# dsky_md_2_4v.net
KiCad netlist of a schematic drawn in EAGLE
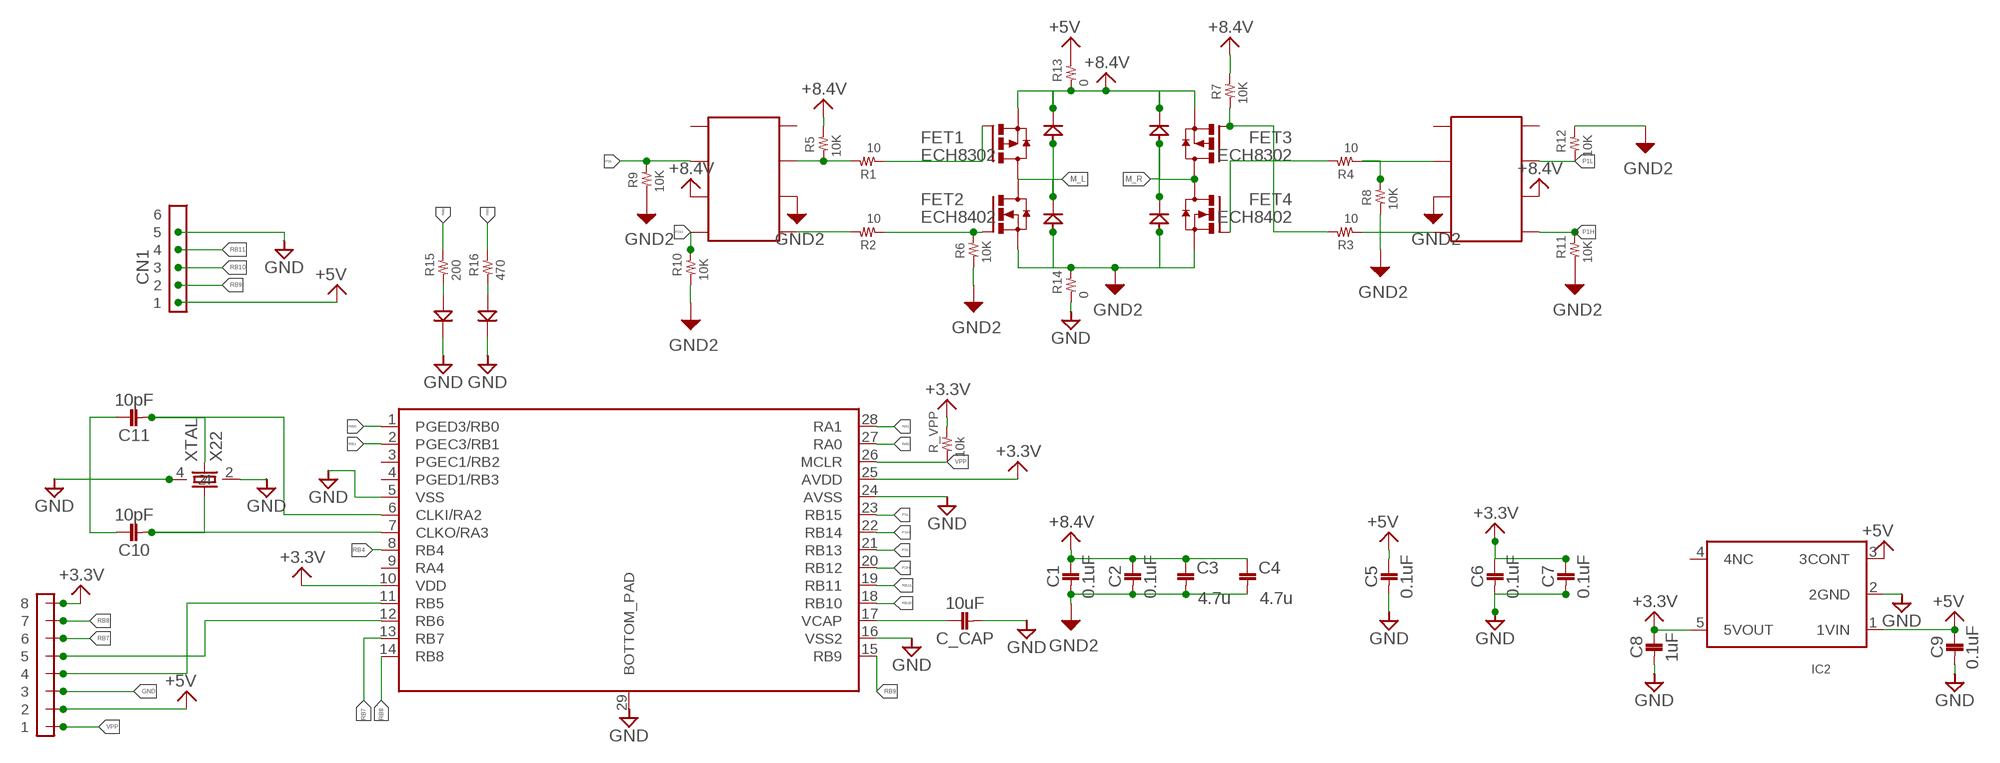
[diagram p0: schematic, sheet 1]

(export (version "E")
  (design (tool "Eeschema 10.0.6"))
  (components
    (comp (ref "C1")
      (value "0.1uF")
      (footprint "eagle-import:1608")
      (libsource (lib "eagle-import") (part "1608"))
    )
    (comp (ref "C2")
      (value "0.1uF")
      (footprint "eagle-import:1608")
      (libsource (lib "eagle-import") (part "1608"))
    )
    (comp (ref "C3")
      (value "4.7u")
      (footprint "eagle-import:2012")
      (libsource (lib "eagle-import") (part "2012"))
    )
    (comp (ref "C4")
      (value "4.7u")
      (footprint "eagle-import:2012")
      (libsource (lib "eagle-import") (part "2012"))
    )
    (comp (ref "C5")
      (value "0.1uF")
      (footprint "eagle-import:1608")
      (libsource (lib "eagle-import") (part "1608"))
    )
    (comp (ref "C6")
      (value "0.1uF")
      (footprint "eagle-import:1608")
      (libsource (lib "eagle-import") (part "1608"))
    )
    (comp (ref "C7")
      (value "0.1uF")
      (footprint "eagle-import:1608")
      (libsource (lib "eagle-import") (part "1608"))
    )
    (comp (ref "C8")
      (value "1uF")
      (footprint "eagle-import:1608")
      (libsource (lib "eagle-import") (part "1608"))
    )
    (comp (ref "C9")
      (value "0.1uF")
      (footprint "eagle-import:1608")
      (libsource (lib "eagle-import") (part "1608"))
    )
    (comp (ref "C10")
      (value "10pF")
      (footprint "eagle-import:1608")
      (libsource (lib "eagle-import") (part "1608"))
    )
    (comp (ref "C11")
      (value "10pF")
      (footprint "eagle-import:1608")
      (libsource (lib "eagle-import") (part "1608"))
    )
    (comp (ref "CN1")
      (value "FH12-6S-0.5")
      (footprint "eagle-import:FPC6")
      (libsource (lib "eagle-import") (part "FH12-6S-0.5"))
    )
    (comp (ref "C_CAP")
      (value "10uF")
      (footprint "eagle-import:1608")
      (libsource (lib "eagle-import") (part "1608"))
    )
    (comp (ref "D1")
      (value "SS2040")
      (footprint "eagle-import:SOD-123FL")
      (libsource (lib "eagle-import") (part "SS2040"))
    )
    (comp (ref "D2")
      (value "SS2040")
      (footprint "eagle-import:SOD-123FL")
      (libsource (lib "eagle-import") (part "SS2040"))
    )
    (comp (ref "D3")
      (value "SS2040")
      (footprint "eagle-import:SOD-123FL")
      (libsource (lib "eagle-import") (part "SS2040"))
    )
    (comp (ref "D4")
      (value "SS2040")
      (footprint "eagle-import:SOD-123FL")
      (libsource (lib "eagle-import") (part "SS2040"))
    )
    (comp (ref "FET1")
      (value "ECH8302")
      (footprint "eagle-import:ECH8")
      (libsource (lib "eagle-import") (part "ECH83"))
    )
    (comp (ref "FET2")
      (value "ECH8402")
      (footprint "eagle-import:ECH8")
      (libsource (lib "eagle-import") (part "ECH84"))
    )
    (comp (ref "FET3")
      (value "ECH8302")
      (footprint "eagle-import:ECH8")
      (libsource (lib "eagle-import") (part "ECH83"))
    )
    (comp (ref "FET4")
      (value "ECH8402")
      (footprint "eagle-import:ECH8")
      (libsource (lib "eagle-import") (part "ECH84"))
    )
    (comp (ref "IC1")
      (value "DSPIC33EP32MC202")
      (footprint "eagle-import:QFN-S28_6X6MC")
      (libsource (lib "eagle-import") (part "DSPIC33EP32MC202"))
    )
    (comp (ref "IC2")
      (value "NJM2866F33")
      (footprint "eagle-import:SSOP5-P-0.95")
      (libsource (lib "eagle-import") (part "TAR5SB"))
    )
    (comp (ref "IC3")
      (value "TC1427COA")
      (footprint "eagle-import:SOIC8")
      (libsource (lib "eagle-import") (part "TC1427COA"))
    )
    (comp (ref "IC4")
      (value "TC1427COA")
      (footprint "eagle-import:SOIC8")
      (libsource (lib "eagle-import") (part "TC1427COA"))
    )
    (comp (ref "LED1")
      (value "1608")
      (footprint "eagle-import:1608")
      (libsource (lib "eagle-import") (part "LED_1608"))
    )
    (comp (ref "LED2")
      (value "1608")
      (footprint "eagle-import:1608")
      (libsource (lib "eagle-import") (part "LED_1608"))
    )
    (comp (ref "PIN_HEADER")
      (value "PIN_HEADER_8")
      (footprint "eagle-import:PIN_HEADER_8")
      (libsource (lib "eagle-import") (part "PIN_HEADER_8"))
    )
    (comp (ref "R1")
      (value "10")
      (footprint "eagle-import:1608")
      (libsource (lib "eagle-import") (part "RESISTOR__SMD"))
    )
    (comp (ref "R2")
      (value "10")
      (footprint "eagle-import:1608")
      (libsource (lib "eagle-import") (part "RESISTOR__SMD"))
    )
    (comp (ref "R3")
      (value "10")
      (footprint "eagle-import:1608")
      (libsource (lib "eagle-import") (part "RESISTOR__SMD"))
    )
    (comp (ref "R4")
      (value "10")
      (footprint "eagle-import:1608")
      (libsource (lib "eagle-import") (part "RESISTOR__SMD"))
    )
    (comp (ref "R5")
      (value "10K")
      (footprint "eagle-import:1608")
      (libsource (lib "eagle-import") (part "RESISTOR__SMD"))
    )
    (comp (ref "R6")
      (value "10K")
      (footprint "eagle-import:1608")
      (libsource (lib "eagle-import") (part "RESISTOR__SMD"))
    )
    (comp (ref "R7")
      (value "10K")
      (footprint "eagle-import:1608")
      (libsource (lib "eagle-import") (part "RESISTOR__SMD"))
    )
    (comp (ref "R8")
      (value "10K")
      (footprint "eagle-import:1608")
      (libsource (lib "eagle-import") (part "RESISTOR__SMD"))
    )
    (comp (ref "R9")
      (value "10K")
      (footprint "eagle-import:1608")
      (libsource (lib "eagle-import") (part "RESISTOR__SMD"))
    )
    (comp (ref "R10")
      (value "10K")
      (footprint "eagle-import:1608")
      (libsource (lib "eagle-import") (part "RESISTOR__SMD"))
    )
    (comp (ref "R11")
      (value "10K")
      (footprint "eagle-import:1608")
      (libsource (lib "eagle-import") (part "RESISTOR__SMD"))
    )
    (comp (ref "R12")
      (value "10K")
      (footprint "eagle-import:1608")
      (libsource (lib "eagle-import") (part "RESISTOR__SMD"))
    )
    (comp (ref "R13")
      (value "0")
      (footprint "eagle-import:1608")
      (libsource (lib "eagle-import") (part "RESISTOR__SMD"))
    )
    (comp (ref "R14")
      (value "0")
      (footprint "eagle-import:1608")
      (libsource (lib "eagle-import") (part "RESISTOR__SMD"))
    )
    (comp (ref "R15")
      (value "200")
      (footprint "eagle-import:1608")
      (libsource (lib "eagle-import") (part "RESISTOR__SMD"))
    )
    (comp (ref "R16")
      (value "470")
      (footprint "eagle-import:1608")
      (libsource (lib "eagle-import") (part "RESISTOR__SMD"))
    )
    (comp (ref "R_VPP")
      (value "10k")
      (footprint "eagle-import:1608")
      (libsource (lib "eagle-import") (part "RESISTOR__SMD"))
    )
    (comp (ref "XTAL")
      (value "X22")
      (footprint "eagle-import:SMD_X22")
      (libsource (lib "eagle-import") (part "X22"))
    )
  )
  (nets
    (net (code "1") (name "+3.3V") (class "Default")
      (node (ref "C6") (pin "P$1") (pinfunction "1_P$1") (pintype "passive"))
      (node (ref "C7") (pin "P$1") (pinfunction "1_P$1") (pintype "passive"))
      (node (ref "C8") (pin "P$1") (pinfunction "1_P$1") (pintype "passive"))
      (node (ref "IC1") (pin "10") (pinfunction "VDD_10") (pintype "bidirectional"))
      (node (ref "IC1") (pin "25") (pinfunction "AVDD_25") (pintype "bidirectional"))
      (node (ref "IC2") (pin "5") (pinfunction "5VOUT_5") (pintype "bidirectional"))
      (node (ref "PIN_HEADER") (pin "8") (pinfunction "8_8") (pintype "bidirectional"))
      (node (ref "R_VPP") (pin "2") (pinfunction "P$2_2") (pintype "passive"))
    )
    (net (code "2") (name "+5V") (class "Default")
      (node (ref "C5") (pin "P$1") (pinfunction "1_P$1") (pintype "passive"))
      (node (ref "C9") (pin "P$1") (pinfunction "1_P$1") (pintype "passive"))
      (node (ref "CN1") (pin "P1") (pinfunction "1_P1") (pintype "bidirectional"))
      (node (ref "IC2") (pin "1") (pinfunction "1VIN_1") (pintype "bidirectional"))
      (node (ref "IC2") (pin "3") (pinfunction "3CONT_3") (pintype "bidirectional"))
      (node (ref "PIN_HEADER") (pin "2") (pinfunction "2_2") (pintype "bidirectional"))
      (node (ref "R13") (pin "2") (pinfunction "P$2_2") (pintype "passive"))
    )
    (net (code "3") (name "+8.4V") (class "Default")
      (node (ref "C1") (pin "P$1") (pinfunction "1_P$1") (pintype "passive"))
      (node (ref "C2") (pin "P$1") (pinfunction "1_P$1") (pintype "passive"))
      (node (ref "C3") (pin "1") (pinfunction "1_1") (pintype "passive"))
      (node (ref "C4") (pin "1") (pinfunction "1_1") (pintype "passive"))
      (node (ref "D1") (pin "2") (pinfunction "PK_2") (pintype "bidirectional"))
      (node (ref "D3") (pin "2") (pinfunction "PK_2") (pintype "bidirectional"))
      (node (ref "FET1") (pin "1") (pinfunction "S_1") (pintype "passive"))
      (node (ref "FET1") (pin "2") (pinfunction "S_2") (pintype "passive"))
      (node (ref "FET1") (pin "3") (pinfunction "S_3") (pintype "passive"))
      (node (ref "FET3") (pin "1") (pinfunction "S_1") (pintype "passive"))
      (node (ref "FET3") (pin "2") (pinfunction "S_2") (pintype "passive"))
      (node (ref "FET3") (pin "3") (pinfunction "S_3") (pintype "passive"))
      (node (ref "IC3") (pin "3") (pinfunction "3_GND_3") (pintype "bidirectional"))
      (node (ref "IC4") (pin "3") (pinfunction "3_GND_3") (pintype "bidirectional"))
      (node (ref "R13") (pin "1") (pinfunction "P$1_1") (pintype "passive"))
      (node (ref "R5") (pin "2") (pinfunction "P$2_2") (pintype "passive"))
      (node (ref "R7") (pin "2") (pinfunction "P$2_2") (pintype "passive"))
    )
    (net (code "4") (name "GND") (class "Default")
      (node (ref "C10") (pin "P$1") (pinfunction "1_P$1") (pintype "passive"))
      (node (ref "C11") (pin "P$1") (pinfunction "1_P$1") (pintype "passive"))
      (node (ref "C5") (pin "P$2") (pinfunction "2_P$2") (pintype "passive"))
      (node (ref "C6") (pin "P$2") (pinfunction "2_P$2") (pintype "passive"))
      (node (ref "C7") (pin "P$2") (pinfunction "2_P$2") (pintype "passive"))
      (node (ref "C8") (pin "P$2") (pinfunction "2_P$2") (pintype "passive"))
      (node (ref "C9") (pin "P$2") (pinfunction "2_P$2") (pintype "passive"))
      (node (ref "CN1") (pin "P5") (pinfunction "5_P5") (pintype "bidirectional"))
      (node (ref "CN1") (pin "P_NC1") (pinfunction "5_P_NC1") (pintype "bidirectional"))
      (node (ref "CN1") (pin "P_NC2") (pinfunction "5_P_NC2") (pintype "bidirectional"))
      (node (ref "C_CAP") (pin "P$2") (pinfunction "2_P$2") (pintype "passive"))
      (node (ref "IC1") (pin "16") (pinfunction "VSS2_16") (pintype "power_in"))
      (node (ref "IC1") (pin "24") (pinfunction "AVSS_24") (pintype "bidirectional"))
      (node (ref "IC1") (pin "29") (pinfunction "BOTTOM_PAD_29") (pintype "bidirectional"))
      (node (ref "IC1") (pin "5") (pinfunction "VSS_5") (pintype "power_in"))
      (node (ref "IC2") (pin "2") (pinfunction "2GND_2") (pintype "bidirectional"))
      (node (ref "LED1") (pin "2") (pinfunction "K_2") (pintype "bidirectional"))
      (node (ref "LED2") (pin "2") (pinfunction "K_2") (pintype "bidirectional"))
      (node (ref "PIN_HEADER") (pin "3") (pinfunction "3_3") (pintype "bidirectional"))
      (node (ref "R14") (pin "1") (pinfunction "P$1_1") (pintype "passive"))
      (node (ref "XTAL") (pin "2") (pinfunction "2_2") (pintype "bidirectional"))
      (node (ref "XTAL") (pin "4") (pinfunction "4_4") (pintype "bidirectional"))
    )
    (net (code "5") (name "GND2") (class "Default")
      (node (ref "C1") (pin "P$2") (pinfunction "2_P$2") (pintype "passive"))
      (node (ref "C2") (pin "P$2") (pinfunction "2_P$2") (pintype "passive"))
      (node (ref "C3") (pin "2") (pinfunction "2_2") (pintype "passive"))
      (node (ref "C4") (pin "2") (pinfunction "2_2") (pintype "passive"))
      (node (ref "D2") (pin "1") (pinfunction "PA_1") (pintype "bidirectional"))
      (node (ref "D4") (pin "1") (pinfunction "PA_1") (pintype "bidirectional"))
      (node (ref "FET2") (pin "1") (pinfunction "S_1") (pintype "passive"))
      (node (ref "FET2") (pin "2") (pinfunction "S_2") (pintype "passive"))
      (node (ref "FET2") (pin "3") (pinfunction "S_3") (pintype "passive"))
      (node (ref "FET4") (pin "1") (pinfunction "S_1") (pintype "passive"))
      (node (ref "FET4") (pin "2") (pinfunction "S_2") (pintype "passive"))
      (node (ref "FET4") (pin "3") (pinfunction "S_3") (pintype "passive"))
      (node (ref "IC3") (pin "6") (pinfunction "6_VDD_6") (pintype "bidirectional"))
      (node (ref "IC4") (pin "6") (pinfunction "6_VDD_6") (pintype "bidirectional"))
      (node (ref "R10") (pin "1") (pinfunction "P$1_1") (pintype "passive"))
      (node (ref "R11") (pin "1") (pinfunction "P$1_1") (pintype "passive"))
      (node (ref "R12") (pin "2") (pinfunction "P$2_2") (pintype "passive"))
      (node (ref "R14") (pin "2") (pinfunction "P$2_2") (pintype "passive"))
      (node (ref "R6") (pin "1") (pinfunction "P$1_1") (pintype "passive"))
      (node (ref "R8") (pin "1") (pinfunction "P$1_1") (pintype "passive"))
      (node (ref "R9") (pin "1") (pinfunction "P$1_1") (pintype "passive"))
    )
    (net (code "6") (name "M_L") (class "Default")
      (node (ref "D1") (pin "1") (pinfunction "PA_1") (pintype "bidirectional"))
      (node (ref "D2") (pin "2") (pinfunction "PK_2") (pintype "bidirectional"))
      (node (ref "FET1") (pin "5") (pinfunction "D_5") (pintype "passive"))
      (node (ref "FET1") (pin "6") (pinfunction "D_6") (pintype "passive"))
      (node (ref "FET1") (pin "7") (pinfunction "D_7") (pintype "passive"))
      (node (ref "FET1") (pin "8") (pinfunction "D_8") (pintype "passive"))
      (node (ref "FET2") (pin "5") (pinfunction "D_5") (pintype "passive"))
      (node (ref "FET2") (pin "6") (pinfunction "D_6") (pintype "passive"))
      (node (ref "FET2") (pin "7") (pinfunction "D_7") (pintype "passive"))
      (node (ref "FET2") (pin "8") (pinfunction "D_8") (pintype "passive"))
    )
    (net (code "7") (name "M_R") (class "Default")
      (node (ref "D3") (pin "1") (pinfunction "PA_1") (pintype "bidirectional"))
      (node (ref "D4") (pin "2") (pinfunction "PK_2") (pintype "bidirectional"))
      (node (ref "FET3") (pin "5") (pinfunction "D_5") (pintype "passive"))
      (node (ref "FET3") (pin "6") (pinfunction "D_6") (pintype "passive"))
      (node (ref "FET3") (pin "7") (pinfunction "D_7") (pintype "passive"))
      (node (ref "FET3") (pin "8") (pinfunction "D_8") (pintype "passive"))
      (node (ref "FET4") (pin "5") (pinfunction "D_5") (pintype "passive"))
      (node (ref "FET4") (pin "6") (pinfunction "D_6") (pintype "passive"))
      (node (ref "FET4") (pin "7") (pinfunction "D_7") (pintype "passive"))
      (node (ref "FET4") (pin "8") (pinfunction "D_8") (pintype "passive"))
    )
    (net (code "8") (name "Net-(C10-2)") (class "Default")
      (node (ref "C10") (pin "P$2") (pinfunction "2_P$2") (pintype "passive"))
      (node (ref "IC1") (pin "7") (pinfunction "CLKO/RA3_7") (pintype "bidirectional"))
      (node (ref "XTAL") (pin "1") (pinfunction "1_1") (pintype "passive"))
    )
    (net (code "9") (name "Net-(C11-2)") (class "Default")
      (node (ref "C11") (pin "P$2") (pinfunction "2_P$2") (pintype "passive"))
      (node (ref "IC1") (pin "6") (pinfunction "CLKI/RA2_6") (pintype "bidirectional"))
      (node (ref "XTAL") (pin "3") (pinfunction "3_3") (pintype "passive"))
    )
    (net (code "10") (name "Net-(C_CAP-1)") (class "Default")
      (node (ref "C_CAP") (pin "P$1") (pinfunction "1_P$1") (pintype "passive"))
      (node (ref "IC1") (pin "17") (pinfunction "VCAP_17") (pintype "bidirectional"))
    )
    (net (code "11") (name "Net-(FET1-G)") (class "Default")
      (node (ref "FET1") (pin "4") (pinfunction "G_4") (pintype "passive"))
      (node (ref "R1") (pin "1") (pinfunction "P$1_1") (pintype "passive"))
    )
    (net (code "12") (name "Net-(FET2-G)") (class "Default")
      (node (ref "FET2") (pin "4") (pinfunction "G_4") (pintype "passive"))
      (node (ref "R2") (pin "1") (pinfunction "P$1_1") (pintype "passive"))
      (node (ref "R6") (pin "2") (pinfunction "P$2_2") (pintype "passive"))
    )
    (net (code "13") (name "Net-(FET3-G)") (class "Default")
      (node (ref "FET3") (pin "4") (pinfunction "G_4") (pintype "passive"))
      (node (ref "R3") (pin "2") (pinfunction "P$2_2") (pintype "passive"))
      (node (ref "R7") (pin "1") (pinfunction "P$1_1") (pintype "passive"))
    )
    (net (code "14") (name "Net-(FET4-G)") (class "Default")
      (node (ref "FET4") (pin "4") (pinfunction "G_4") (pintype "passive"))
      (node (ref "R4") (pin "2") (pinfunction "P$2_2") (pintype "passive"))
    )
    (net (code "15") (name "Net-(IC1-RB5)") (class "Default")
      (node (ref "IC1") (pin "11") (pinfunction "RB5_11") (pintype "bidirectional"))
      (node (ref "PIN_HEADER") (pin "4") (pinfunction "4_4") (pintype "bidirectional"))
    )
    (net (code "16") (name "Net-(IC1-RB6)") (class "Default")
      (node (ref "IC1") (pin "12") (pinfunction "RB6_12") (pintype "bidirectional"))
      (node (ref "PIN_HEADER") (pin "5") (pinfunction "5_5") (pintype "bidirectional"))
    )
    (net (code "17") (name "Net-(IC3-5_OUT_B)") (class "Default")
      (node (ref "IC3") (pin "5") (pinfunction "5_OUT_B_5") (pintype "bidirectional"))
      (node (ref "R2") (pin "2") (pinfunction "P$2_2") (pintype "passive"))
    )
    (net (code "18") (name "Net-(IC3-7_OUT_A)") (class "Default")
      (node (ref "IC3") (pin "7") (pinfunction "7_OUT_A_7") (pintype "bidirectional"))
      (node (ref "R1") (pin "2") (pinfunction "P$2_2") (pintype "passive"))
      (node (ref "R5") (pin "1") (pinfunction "P$1_1") (pintype "passive"))
    )
    (net (code "19") (name "Net-(IC4-5_OUT_B)") (class "Default")
      (node (ref "IC4") (pin "5") (pinfunction "5_OUT_B_5") (pintype "bidirectional"))
      (node (ref "R3") (pin "1") (pinfunction "P$1_1") (pintype "passive"))
    )
    (net (code "20") (name "Net-(IC4-7_OUT_A)") (class "Default")
      (node (ref "IC4") (pin "7") (pinfunction "7_OUT_A_7") (pintype "bidirectional"))
      (node (ref "R4") (pin "1") (pinfunction "P$1_1") (pintype "passive"))
      (node (ref "R8") (pin "2") (pinfunction "P$2_2") (pintype "passive"))
    )
    (net (code "21") (name "Net-(LED1-A)") (class "Default")
      (node (ref "LED1") (pin "1") (pinfunction "A_1") (pintype "bidirectional"))
      (node (ref "R15") (pin "1") (pinfunction "P$1_1") (pintype "passive"))
    )
    (net (code "22") (name "Net-(LED2-A)") (class "Default")
      (node (ref "LED2") (pin "1") (pinfunction "A_1") (pintype "bidirectional"))
      (node (ref "R16") (pin "1") (pinfunction "P$1_1") (pintype "passive"))
    )
    (net (code "23") (name "P1H") (class "Default")
      (node (ref "IC1") (pin "22") (pinfunction "RB14_22") (pintype "bidirectional"))
      (node (ref "IC4") (pin "4") (pinfunction "4_IN_B_4") (pintype "bidirectional"))
      (node (ref "R11") (pin "2") (pinfunction "P$2_2") (pintype "passive"))
    )
    (net (code "24") (name "P1L") (class "Default")
      (node (ref "IC1") (pin "23") (pinfunction "RB15_23") (pintype "bidirectional"))
      (node (ref "IC4") (pin "2") (pinfunction "2_IN_A_2") (pintype "bidirectional"))
      (node (ref "R12") (pin "1") (pinfunction "P$1_1") (pintype "passive"))
    )
    (net (code "25") (name "P2H") (class "Default")
      (node (ref "IC1") (pin "20") (pinfunction "RB12_20") (pintype "bidirectional"))
      (node (ref "IC3") (pin "4") (pinfunction "4_IN_B_4") (pintype "bidirectional"))
      (node (ref "R10") (pin "2") (pinfunction "P$2_2") (pintype "passive"))
    )
    (net (code "26") (name "P2L") (class "Default")
      (node (ref "IC1") (pin "21") (pinfunction "RB13_21") (pintype "bidirectional"))
      (node (ref "IC3") (pin "2") (pinfunction "2_IN_A_2") (pintype "bidirectional"))
      (node (ref "R9") (pin "2") (pinfunction "P$2_2") (pintype "passive"))
    )
    (net (code "27") (name "RA0") (class "Default")
      (node (ref "IC1") (pin "27") (pinfunction "RA0_27") (pintype "bidirectional"))
      (node (ref "R15") (pin "2") (pinfunction "P$2_2") (pintype "passive"))
    )
    (net (code "28") (name "RA1") (class "Default")
      (node (ref "IC1") (pin "28") (pinfunction "RA1_28") (pintype "bidirectional"))
    )
    (net (code "29") (name "RB0") (class "Default")
      (node (ref "IC1") (pin "1") (pinfunction "PGED3/RB0_1") (pintype "bidirectional"))
      (node (ref "R16") (pin "2") (pinfunction "P$2_2") (pintype "passive"))
    )
    (net (code "30") (name "RB1") (class "Default")
      (node (ref "IC1") (pin "2") (pinfunction "PGEC3/RB1_2") (pintype "bidirectional"))
    )
    (net (code "31") (name "RB4") (class "Default")
      (node (ref "IC1") (pin "8") (pinfunction "RB4_8") (pintype "bidirectional"))
    )
    (net (code "32") (name "RB7") (class "Default")
      (node (ref "IC1") (pin "13") (pinfunction "RB7_13") (pintype "bidirectional"))
      (node (ref "PIN_HEADER") (pin "6") (pinfunction "6_6") (pintype "bidirectional"))
    )
    (net (code "33") (name "RB8") (class "Default")
      (node (ref "IC1") (pin "14") (pinfunction "RB8_14") (pintype "bidirectional"))
      (node (ref "PIN_HEADER") (pin "7") (pinfunction "7_7") (pintype "bidirectional"))
    )
    (net (code "34") (name "RB9") (class "Default")
      (node (ref "CN1") (pin "P2") (pinfunction "2_P2") (pintype "bidirectional"))
      (node (ref "IC1") (pin "15") (pinfunction "RB9_15") (pintype "bidirectional"))
    )
    (net (code "35") (name "RB10") (class "Default")
      (node (ref "CN1") (pin "P3") (pinfunction "3_P3") (pintype "bidirectional"))
      (node (ref "IC1") (pin "18") (pinfunction "RB10_18") (pintype "bidirectional"))
    )
    (net (code "36") (name "RB11") (class "Default")
      (node (ref "CN1") (pin "P4") (pinfunction "4_P4") (pintype "bidirectional"))
      (node (ref "IC1") (pin "19") (pinfunction "RB11_19") (pintype "bidirectional"))
    )
    (net (code "37") (name "VPP") (class "Default")
      (node (ref "IC1") (pin "26") (pinfunction "MCLR_26") (pintype "bidirectional"))
      (node (ref "PIN_HEADER") (pin "1") (pinfunction "1_1") (pintype "bidirectional"))
      (node (ref "R_VPP") (pin "1") (pinfunction "P$1_1") (pintype "passive"))
    )
    (net (code "38") (name "unconnected-(CN1-6-PadP6)") (class "Default")
      (node (ref "CN1") (pin "P6") (pinfunction "6_P6") (pintype "bidirectional"))
    )
    (net (code "39") (name "unconnected-(IC1-PGEC1{slash}RB2-Pad3)") (class "Default")
      (node (ref "IC1") (pin "3") (pinfunction "PGEC1/RB2_3") (pintype "bidirectional"))
    )
    (net (code "40") (name "unconnected-(IC1-PGED1{slash}RB3-Pad4)") (class "Default")
      (node (ref "IC1") (pin "4") (pinfunction "PGED1/RB3_4") (pintype "bidirectional"))
    )
    (net (code "41") (name "unconnected-(IC1-RA4-Pad9)") (class "Default")
      (node (ref "IC1") (pin "9") (pinfunction "RA4_9") (pintype "bidirectional"))
    )
    (net (code "42") (name "unconnected-(IC2-4NC-Pad4)") (class "Default")
      (node (ref "IC2") (pin "4") (pinfunction "4NC_4") (pintype "bidirectional"))
    )
    (net (code "43") (name "unconnected-(IC3-1_NC-Pad1)") (class "Default")
      (node (ref "IC3") (pin "1") (pinfunction "1_NC_1") (pintype "bidirectional"))
    )
    (net (code "44") (name "unconnected-(IC3-8_NC-Pad8)") (class "Default")
      (node (ref "IC3") (pin "8") (pinfunction "8_NC_8") (pintype "bidirectional"))
    )
    (net (code "45") (name "unconnected-(IC4-1_NC-Pad1)") (class "Default")
      (node (ref "IC4") (pin "1") (pinfunction "1_NC_1") (pintype "bidirectional"))
    )
    (net (code "46") (name "unconnected-(IC4-8_NC-Pad8)") (class "Default")
      (node (ref "IC4") (pin "8") (pinfunction "8_NC_8") (pintype "bidirectional"))
    )
  )
)
